# attiny85_soap.net
KiCad netlist of a schematic drawn in EAGLE
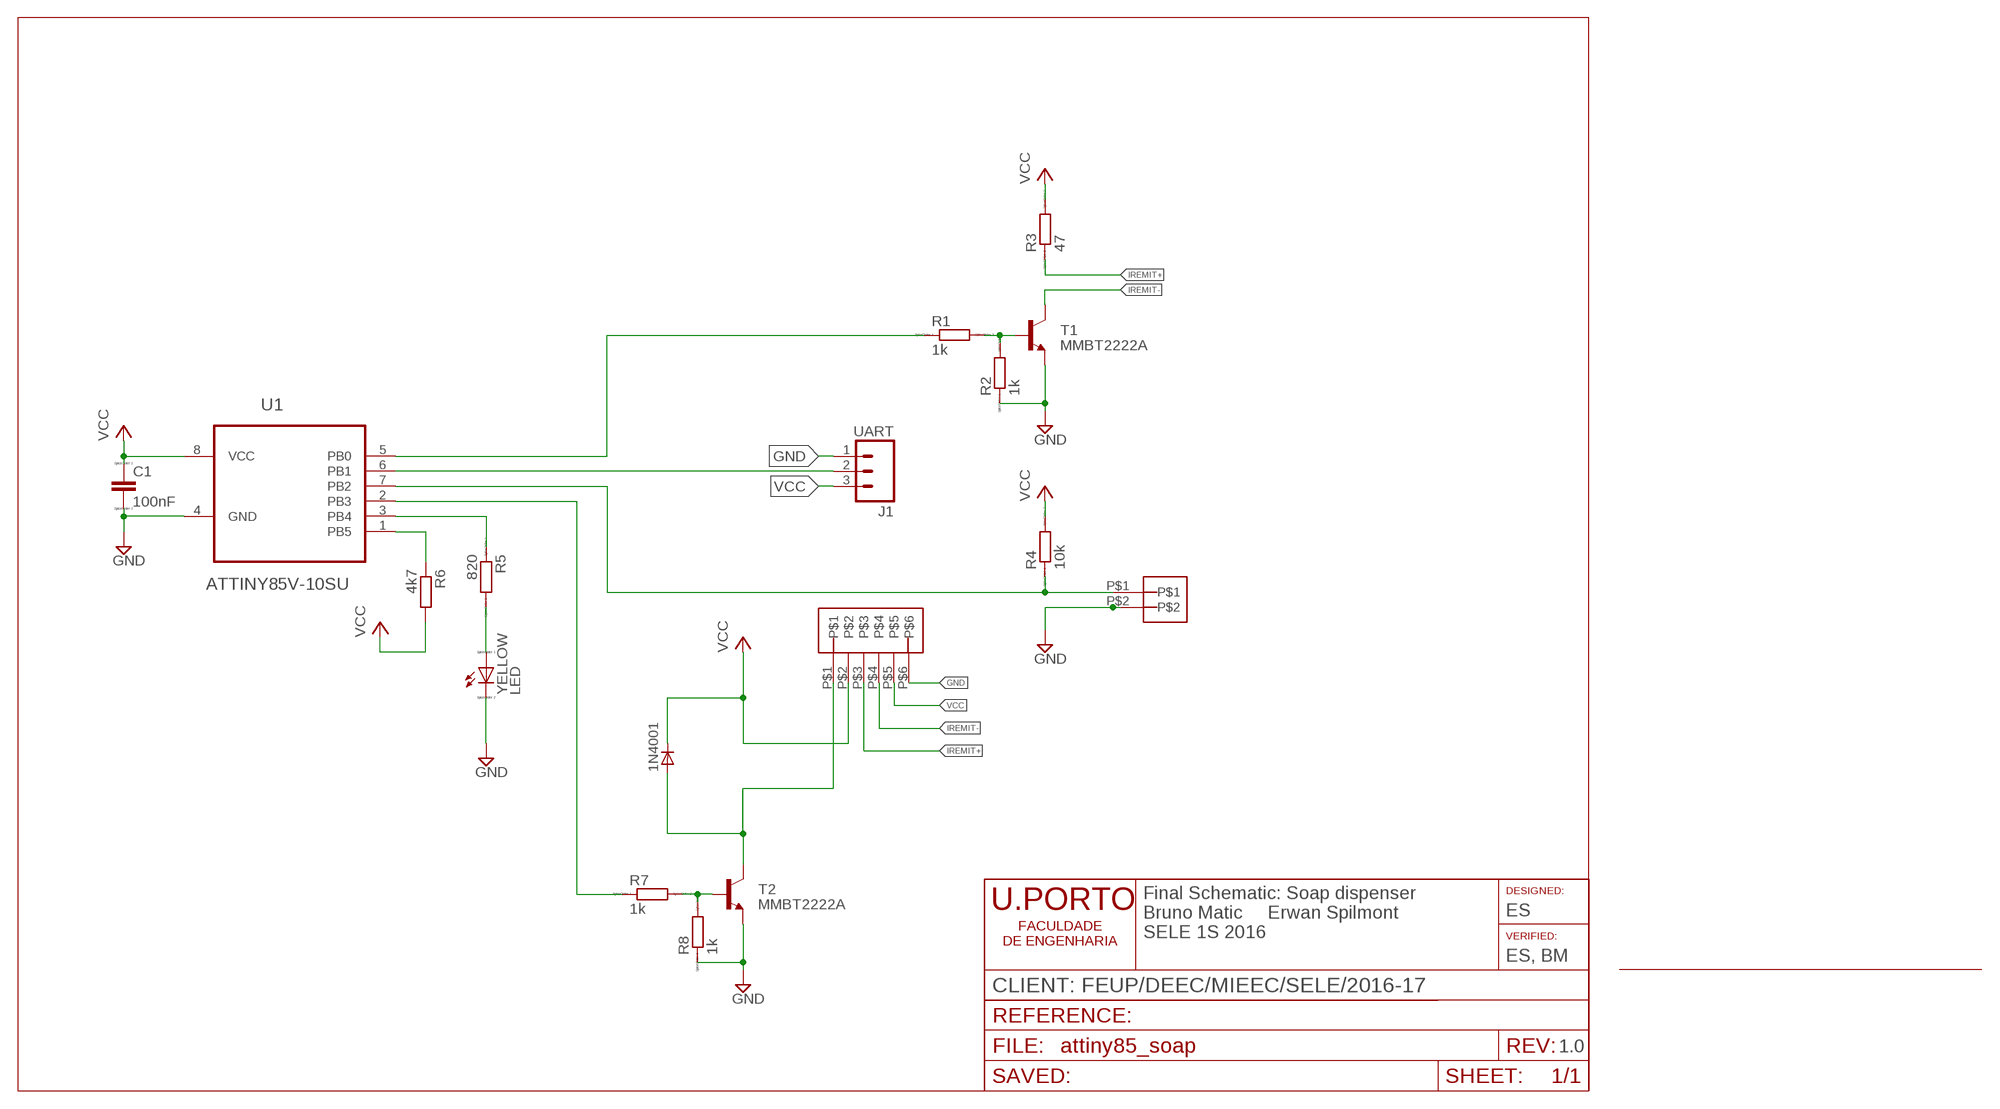
[diagram p0: schematic, sheet 1]

(export (version "E")
  (design (tool "Eeschema 10.0.6"))
  (components
    (comp (ref "1N4001")
      (value "SM400GENERIC")
      (footprint "eagle-import:MELF-MLL41_DO213AB")
      (libsource (lib "eagle-import") (part "SM400GENERIC"))
    )
    (comp (ref "C1")
      (value "100nF")
      (footprint "eagle-import:C0603")
      (libsource (lib "eagle-import") (part "CC0603"))
    )
    (comp (ref "IRDET_CON")
      (value "2_PIN_JST-XH")
      (footprint "eagle-import:2_PIN_JST-XH")
      (libsource (lib "eagle-import") (part "2_PIN_JST-XH"))
    )
    (comp (ref "J1")
      (value "UART")
      (footprint "eagle-import:1X03_NO_SILK")
      (libsource (lib "eagle-import") (part "M031X03_NO_SILK"))
    )
    (comp (ref "R1")
      (value "1k")
      (footprint "eagle-import:R0805")
      (libsource (lib "eagle-import") (part "R"))
    )
    (comp (ref "R2")
      (value "1k")
      (footprint "eagle-import:R0805")
      (libsource (lib "eagle-import") (part "R"))
    )
    (comp (ref "R3")
      (value "47")
      (footprint "eagle-import:R0805")
      (libsource (lib "eagle-import") (part "R"))
    )
    (comp (ref "R4")
      (value "10k")
      (footprint "eagle-import:R0805")
      (libsource (lib "eagle-import") (part "R"))
    )
    (comp (ref "R5")
      (value "820")
      (footprint "eagle-import:R0805")
      (libsource (lib "eagle-import") (part "R"))
    )
    (comp (ref "R6")
      (value "4k7")
      (footprint "eagle-import:R0805")
      (libsource (lib "eagle-import") (part "R-EU_R0805"))
    )
    (comp (ref "R7")
      (value "1k")
      (footprint "eagle-import:R0805")
      (libsource (lib "eagle-import") (part "R"))
    )
    (comp (ref "R8")
      (value "1k")
      (footprint "eagle-import:R0805")
      (libsource (lib "eagle-import") (part "R"))
    )
    (comp (ref "T1")
      (value "MMBT2222A")
      (footprint "eagle-import:SOT23-BEC")
      (libsource (lib "eagle-import") (part "-NPN-SOT23-BECMMBT2222ALT1"))
    )
    (comp (ref "T2")
      (value "MMBT2222A")
      (footprint "eagle-import:SOT23-BEC")
      (libsource (lib "eagle-import") (part "-NPN-SOT23-BECMMBT2222ALT1"))
    )
    (comp (ref "U$1")
      (value "6_PIN_JST-XH")
      (footprint "eagle-import:6_PIN_JST-XH")
      (libsource (lib "eagle-import") (part "6_PIN_JST-XH"))
    )
    (comp (ref "U1")
      (value "ATTINY85V-10SU")
      (footprint "eagle-import:SOIC127P798X216-8N")
      (libsource (lib "eagle-import") (part "ATTINY85V-10SU"))
    )
    (comp (ref "YELLOW")
      (value "LED")
      (footprint "eagle-import:LED_LD260")
      (libsource (lib "eagle-import") (part "LED_ELD260"))
    )
  )
  (nets
    (net (code "1") (name "GND") (class "Default")
      (node (ref "C1") (pin "2") (pinfunction "2_2") (pintype "passive"))
      (node (ref "IRDET_CON") (pin "P$2") (pinfunction "P$2_P$2") (pintype "bidirectional"))
      (node (ref "J1") (pin "1") (pinfunction "1_1") (pintype "passive"))
      (node (ref "R2") (pin "1") (pinfunction "1_1") (pintype "passive"))
      (node (ref "R8") (pin "1") (pinfunction "1_1") (pintype "passive"))
      (node (ref "T1") (pin "E") (pinfunction "E_E") (pintype "passive"))
      (node (ref "T2") (pin "E") (pinfunction "E_E") (pintype "passive"))
      (node (ref "U$1") (pin "P$6") (pinfunction "P$6_P$6") (pintype "bidirectional"))
      (node (ref "U1") (pin "4") (pinfunction "GND_4") (pintype "passive"))
      (node (ref "YELLOW") (pin "K") (pinfunction "C_K") (pintype "passive"))
    )
    (net (code "2") (name "IREMIT+") (class "Default")
      (node (ref "R3") (pin "1") (pinfunction "1_1") (pintype "passive"))
      (node (ref "U$1") (pin "P$3") (pinfunction "P$3_P$3") (pintype "bidirectional"))
    )
    (net (code "3") (name "IREMIT-") (class "Default")
      (node (ref "T1") (pin "C") (pinfunction "C_C") (pintype "passive"))
      (node (ref "U$1") (pin "P$4") (pinfunction "P$4_P$4") (pintype "bidirectional"))
    )
    (net (code "4") (name "Net-(1N4001-PadA)") (class "Default")
      (node (ref "1N4001") (pin "A") (pinfunction "A_A") (pintype "passive"))
      (node (ref "T2") (pin "C") (pinfunction "C_C") (pintype "passive"))
      (node (ref "U$1") (pin "P$1") (pinfunction "P$1_P$1") (pintype "bidirectional"))
    )
    (net (code "5") (name "Net-(R1-Pad2)") (class "Default")
      (node (ref "R1") (pin "2") (pinfunction "2_2") (pintype "passive"))
      (node (ref "R2") (pin "2") (pinfunction "2_2") (pintype "passive"))
      (node (ref "T1") (pin "B") (pinfunction "B_B") (pintype "passive"))
    )
    (net (code "6") (name "Net-(R5-Pad2)") (class "Default")
      (node (ref "R5") (pin "2") (pinfunction "2_2") (pintype "passive"))
      (node (ref "YELLOW") (pin "A") (pinfunction "A_A") (pintype "passive"))
    )
    (net (code "7") (name "Net-(R7-Pad2)") (class "Default")
      (node (ref "R7") (pin "2") (pinfunction "2_2") (pintype "passive"))
      (node (ref "R8") (pin "2") (pinfunction "2_2") (pintype "passive"))
      (node (ref "T2") (pin "B") (pinfunction "B_B") (pintype "passive"))
    )
    (net (code "8") (name "Net-(U1-PB0)") (class "Default")
      (node (ref "R1") (pin "1") (pinfunction "1_1") (pintype "passive"))
      (node (ref "U1") (pin "5") (pinfunction "PB0_5") (pintype "bidirectional"))
    )
    (net (code "9") (name "Net-(U1-PB1)") (class "Default")
      (node (ref "J1") (pin "2") (pinfunction "2_2") (pintype "passive"))
      (node (ref "U1") (pin "6") (pinfunction "PB1_6") (pintype "bidirectional"))
    )
    (net (code "10") (name "Net-(U1-PB2)") (class "Default")
      (node (ref "IRDET_CON") (pin "P$1") (pinfunction "P$1_P$1") (pintype "bidirectional"))
      (node (ref "R4") (pin "1") (pinfunction "1_1") (pintype "passive"))
      (node (ref "U1") (pin "7") (pinfunction "PB2_7") (pintype "bidirectional"))
    )
    (net (code "11") (name "Net-(U1-PB3)") (class "Default")
      (node (ref "R7") (pin "1") (pinfunction "1_1") (pintype "passive"))
      (node (ref "U1") (pin "2") (pinfunction "PB3_2") (pintype "bidirectional"))
    )
    (net (code "12") (name "Net-(U1-PB4)") (class "Default")
      (node (ref "R5") (pin "1") (pinfunction "1_1") (pintype "passive"))
      (node (ref "U1") (pin "3") (pinfunction "PB4_3") (pintype "bidirectional"))
    )
    (net (code "13") (name "Net-(U1-PB5)") (class "Default")
      (node (ref "R6") (pin "1") (pinfunction "1_1") (pintype "passive"))
      (node (ref "U1") (pin "1") (pinfunction "PB5_1") (pintype "bidirectional"))
    )
    (net (code "14") (name "VCC") (class "Default")
      (node (ref "1N4001") (pin "C") (pinfunction "C_C") (pintype "passive"))
      (node (ref "C1") (pin "1") (pinfunction "1_1") (pintype "passive"))
      (node (ref "J1") (pin "3") (pinfunction "3_3") (pintype "passive"))
      (node (ref "R3") (pin "2") (pinfunction "2_2") (pintype "passive"))
      (node (ref "R4") (pin "2") (pinfunction "2_2") (pintype "passive"))
      (node (ref "R6") (pin "2") (pinfunction "2_2") (pintype "passive"))
      (node (ref "U$1") (pin "P$2") (pinfunction "P$2_P$2") (pintype "bidirectional"))
      (node (ref "U$1") (pin "P$5") (pinfunction "P$5_P$5") (pintype "bidirectional"))
      (node (ref "U1") (pin "8") (pinfunction "VCC_8") (pintype "power_in"))
    )
  )
)
